# ESP32_xiaoneisai_20260831.net
KiCad netlist of a schematic drawn in EasyEDA Pro
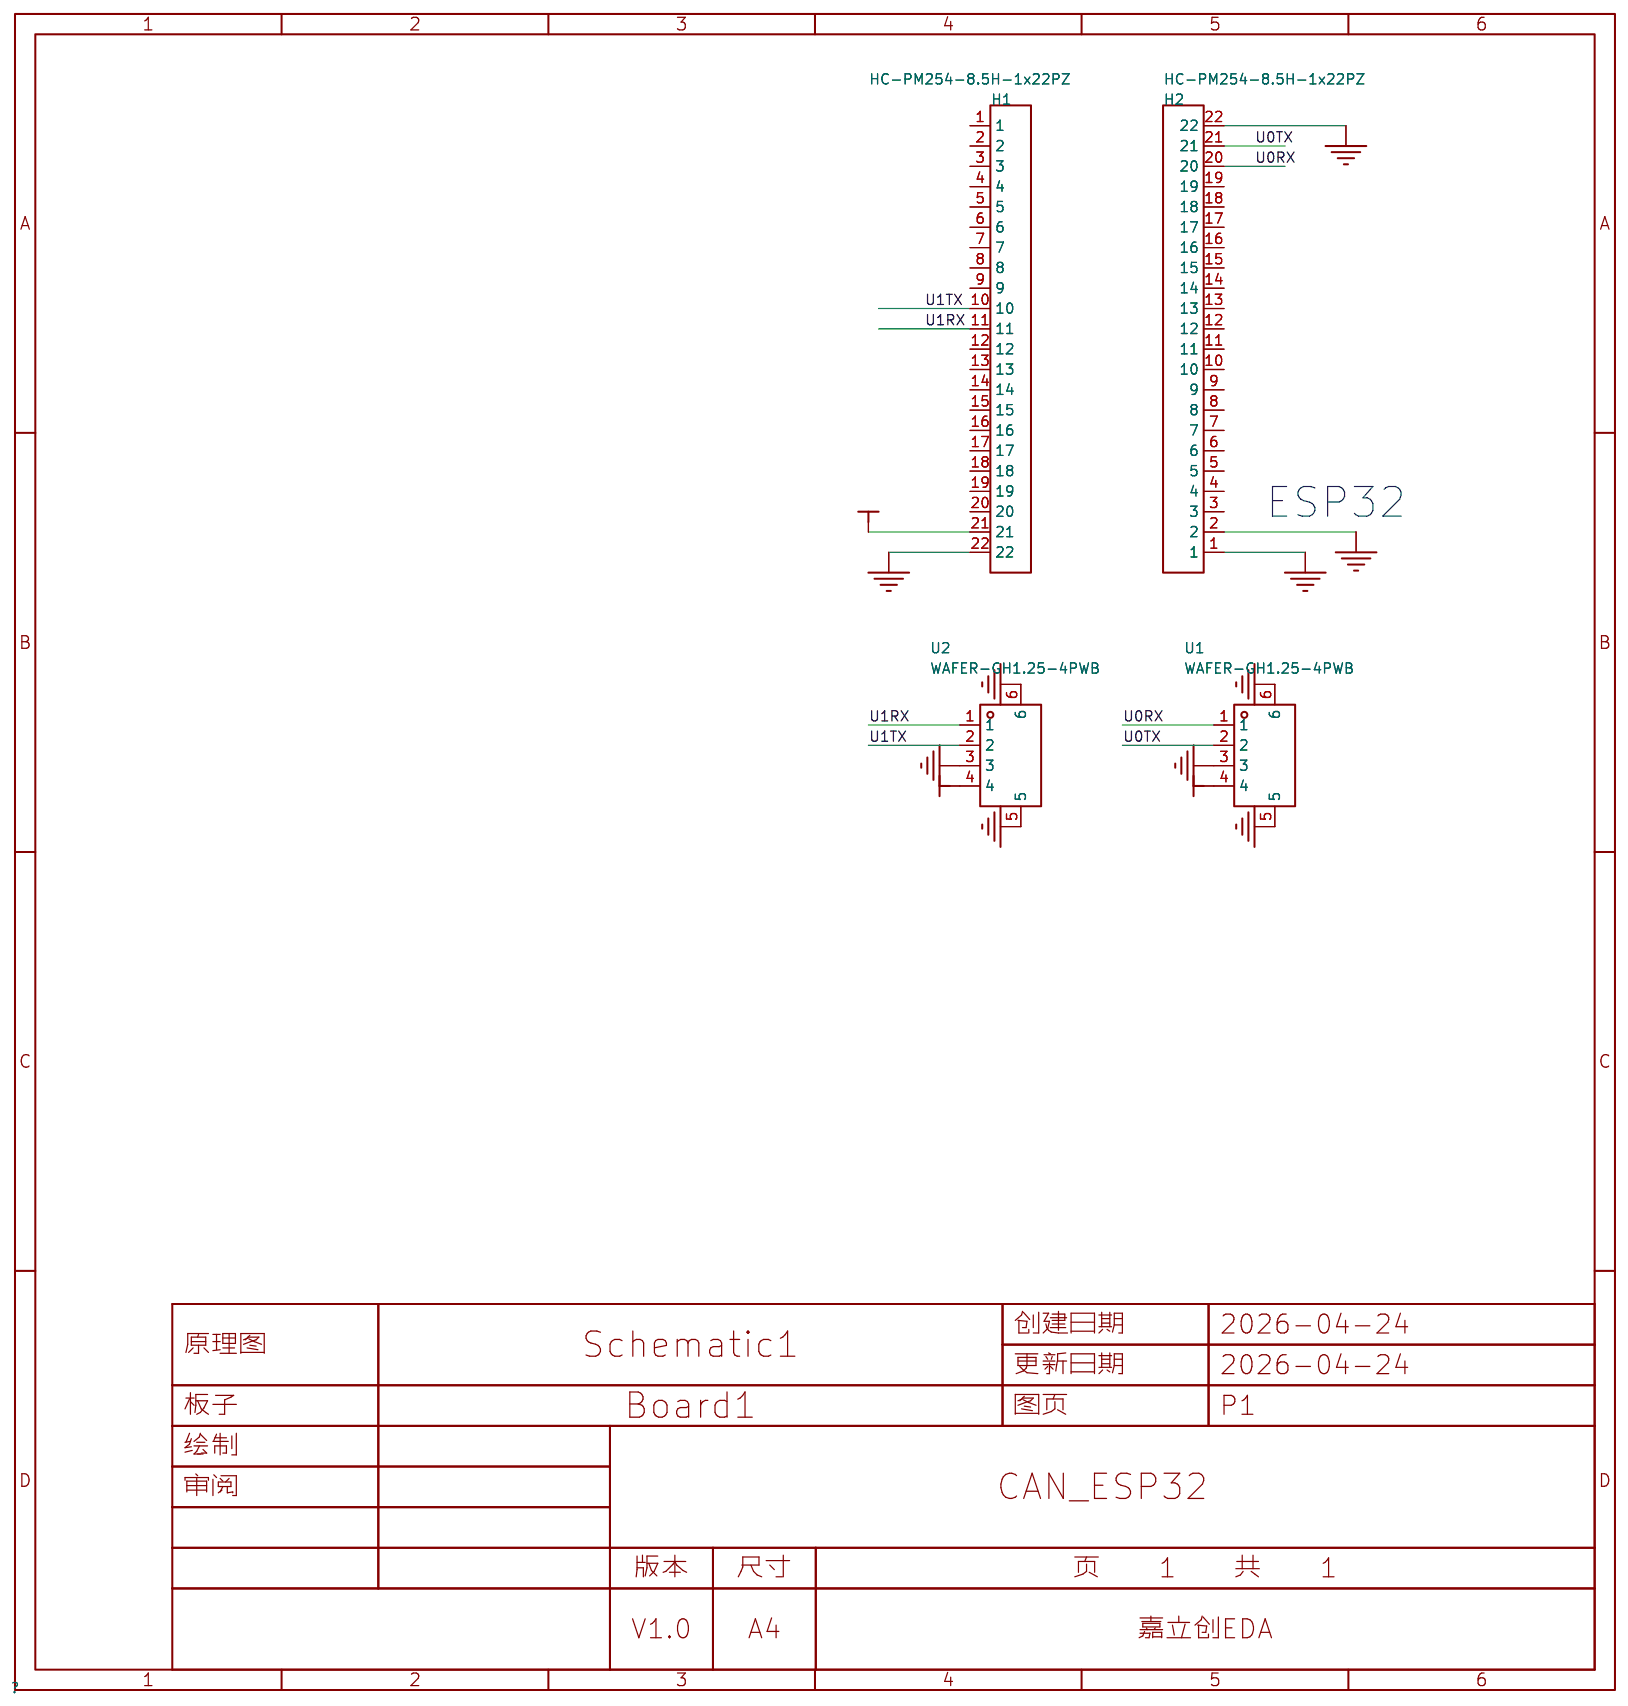
[diagram p0: schematic sheet]

(export (version "E")
  (design (tool "Eeschema 10.0.6"))
  (components
    (comp (ref "H1")
      (value "HC-PM254-8.5H-1x22PZ")
      (footprint "easyedapro:HDR-TH_22P-P2.54-V-F")
      (fields (field (name "Manufacturer") "HC(虹成电子)"))
      (libsource (lib "easyedapro") (part "HC-PM254-8.5H-1X22PZ"))
    )
    (comp (ref "H2")
      (value "HC-PM254-8.5H-1x22PZ")
      (footprint "easyedapro:HDR-TH_22P-P2.54-V-F")
      (fields (field (name "Manufacturer") "HC(虹成电子)"))
      (libsource (lib "easyedapro") (part "HC-PM254-8.5H-1X22PZ"))
    )
    (comp (ref "U1")
      (value "WAFER-GH1.25-4PWB")
      (footprint "easyedapro:CONN-SMD_4P-P1.25_XUNPU_WAFER-GH1.25-4PWB")
      (fields (field (name "Manufacturer") "XUNPU(讯普)"))
      (libsource (lib "easyedapro") (part "WAFER-GH1.25-4PWB"))
    )
    (comp (ref "U2")
      (value "WAFER-GH1.25-4PWB")
      (footprint "easyedapro:CONN-SMD_4P-P1.25_XUNPU_WAFER-GH1.25-4PWB")
      (fields (field (name "Manufacturer") "XUNPU(讯普)"))
      (libsource (lib "easyedapro") (part "WAFER-GH1.25-4PWB"))
    )
  )
  (nets
    (net (code "1") (name "/U0RX") (class "Default")
      (node (ref "H2") (pin "20") (pinfunction "20_20") (pintype "unspecified"))
      (node (ref "U1") (pin "1") (pinfunction "1_1") (pintype "unspecified"))
    )
    (net (code "2") (name "/U0TX") (class "Default")
      (node (ref "H2") (pin "21") (pinfunction "21_21") (pintype "unspecified"))
      (node (ref "U1") (pin "2") (pinfunction "2_2") (pintype "unspecified"))
    )
    (net (code "3") (name "/U1RX") (class "Default")
      (node (ref "H1") (pin "11") (pinfunction "11_11") (pintype "unspecified"))
      (node (ref "U2") (pin "1") (pinfunction "1_1") (pintype "unspecified"))
    )
    (net (code "4") (name "/U1TX") (class "Default")
      (node (ref "H1") (pin "10") (pinfunction "10_10") (pintype "unspecified"))
      (node (ref "U2") (pin "2") (pinfunction "2_2") (pintype "unspecified"))
    )
    (net (code "5") (name "GND") (class "Default")
      (node (ref "H1") (pin "22") (pinfunction "22_22") (pintype "unspecified"))
      (node (ref "H2") (pin "1") (pinfunction "1_1") (pintype "unspecified"))
      (node (ref "H2") (pin "2") (pinfunction "2_2") (pintype "unspecified"))
      (node (ref "H2") (pin "22") (pinfunction "22_22") (pintype "unspecified"))
      (node (ref "U1") (pin "3") (pinfunction "3_3") (pintype "unspecified"))
      (node (ref "U1") (pin "5") (pinfunction "5_5") (pintype "unspecified"))
      (node (ref "U1") (pin "6") (pinfunction "6_6") (pintype "unspecified"))
      (node (ref "U2") (pin "3") (pinfunction "3_3") (pintype "unspecified"))
      (node (ref "U2") (pin "5") (pinfunction "5_5") (pintype "unspecified"))
      (node (ref "U2") (pin "6") (pinfunction "6_6") (pintype "unspecified"))
    )
    (net (code "6") (name "VCC_5V") (class "Default")
      (node (ref "H1") (pin "21") (pinfunction "21_21") (pintype "unspecified"))
      (node (ref "U1") (pin "4") (pinfunction "4_4") (pintype "unspecified"))
      (node (ref "U2") (pin "4") (pinfunction "4_4") (pintype "unspecified"))
    )
    (net (code "7") (name "unconnected-(H1-Pad1)") (class "Default")
      (node (ref "H1") (pin "1") (pinfunction "1_1") (pintype "unspecified"))
    )
    (net (code "8") (name "unconnected-(H1-Pad2)") (class "Default")
      (node (ref "H1") (pin "2") (pinfunction "2_2") (pintype "unspecified"))
    )
    (net (code "9") (name "unconnected-(H1-Pad3)") (class "Default")
      (node (ref "H1") (pin "3") (pinfunction "3_3") (pintype "unspecified"))
    )
    (net (code "10") (name "unconnected-(H1-Pad4)") (class "Default")
      (node (ref "H1") (pin "4") (pinfunction "4_4") (pintype "unspecified"))
    )
    (net (code "11") (name "unconnected-(H1-Pad5)") (class "Default")
      (node (ref "H1") (pin "5") (pinfunction "5_5") (pintype "unspecified"))
    )
    (net (code "12") (name "unconnected-(H1-Pad6)") (class "Default")
      (node (ref "H1") (pin "6") (pinfunction "6_6") (pintype "unspecified"))
    )
    (net (code "13") (name "unconnected-(H1-Pad7)") (class "Default")
      (node (ref "H1") (pin "7") (pinfunction "7_7") (pintype "unspecified"))
    )
    (net (code "14") (name "unconnected-(H1-Pad8)") (class "Default")
      (node (ref "H1") (pin "8") (pinfunction "8_8") (pintype "unspecified"))
    )
    (net (code "15") (name "unconnected-(H1-Pad9)") (class "Default")
      (node (ref "H1") (pin "9") (pinfunction "9_9") (pintype "unspecified"))
    )
    (net (code "16") (name "unconnected-(H1-Pad12)") (class "Default")
      (node (ref "H1") (pin "12") (pinfunction "12_12") (pintype "unspecified"))
    )
    (net (code "17") (name "unconnected-(H1-Pad13)") (class "Default")
      (node (ref "H1") (pin "13") (pinfunction "13_13") (pintype "unspecified"))
    )
    (net (code "18") (name "unconnected-(H1-Pad14)") (class "Default")
      (node (ref "H1") (pin "14") (pinfunction "14_14") (pintype "unspecified"))
    )
    (net (code "19") (name "unconnected-(H1-Pad15)") (class "Default")
      (node (ref "H1") (pin "15") (pinfunction "15_15") (pintype "unspecified"))
    )
    (net (code "20") (name "unconnected-(H1-Pad16)") (class "Default")
      (node (ref "H1") (pin "16") (pinfunction "16_16") (pintype "unspecified"))
    )
    (net (code "21") (name "unconnected-(H1-Pad17)") (class "Default")
      (node (ref "H1") (pin "17") (pinfunction "17_17") (pintype "unspecified"))
    )
    (net (code "22") (name "unconnected-(H1-Pad18)") (class "Default")
      (node (ref "H1") (pin "18") (pinfunction "18_18") (pintype "unspecified"))
    )
    (net (code "23") (name "unconnected-(H1-Pad19)") (class "Default")
      (node (ref "H1") (pin "19") (pinfunction "19_19") (pintype "unspecified"))
    )
    (net (code "24") (name "unconnected-(H1-Pad20)") (class "Default")
      (node (ref "H1") (pin "20") (pinfunction "20_20") (pintype "unspecified"))
    )
    (net (code "25") (name "unconnected-(H2-Pad3)") (class "Default")
      (node (ref "H2") (pin "3") (pinfunction "3_3") (pintype "unspecified"))
    )
    (net (code "26") (name "unconnected-(H2-Pad4)") (class "Default")
      (node (ref "H2") (pin "4") (pinfunction "4_4") (pintype "unspecified"))
    )
    (net (code "27") (name "unconnected-(H2-Pad5)") (class "Default")
      (node (ref "H2") (pin "5") (pinfunction "5_5") (pintype "unspecified"))
    )
    (net (code "28") (name "unconnected-(H2-Pad6)") (class "Default")
      (node (ref "H2") (pin "6") (pinfunction "6_6") (pintype "unspecified"))
    )
    (net (code "29") (name "unconnected-(H2-Pad7)") (class "Default")
      (node (ref "H2") (pin "7") (pinfunction "7_7") (pintype "unspecified"))
    )
    (net (code "30") (name "unconnected-(H2-Pad8)") (class "Default")
      (node (ref "H2") (pin "8") (pinfunction "8_8") (pintype "unspecified"))
    )
    (net (code "31") (name "unconnected-(H2-Pad9)") (class "Default")
      (node (ref "H2") (pin "9") (pinfunction "9_9") (pintype "unspecified"))
    )
    (net (code "32") (name "unconnected-(H2-Pad10)") (class "Default")
      (node (ref "H2") (pin "10") (pinfunction "10_10") (pintype "unspecified"))
    )
    (net (code "33") (name "unconnected-(H2-Pad11)") (class "Default")
      (node (ref "H2") (pin "11") (pinfunction "11_11") (pintype "unspecified"))
    )
    (net (code "34") (name "unconnected-(H2-Pad12)") (class "Default")
      (node (ref "H2") (pin "12") (pinfunction "12_12") (pintype "unspecified"))
    )
    (net (code "35") (name "unconnected-(H2-Pad13)") (class "Default")
      (node (ref "H2") (pin "13") (pinfunction "13_13") (pintype "unspecified"))
    )
    (net (code "36") (name "unconnected-(H2-Pad14)") (class "Default")
      (node (ref "H2") (pin "14") (pinfunction "14_14") (pintype "unspecified"))
    )
    (net (code "37") (name "unconnected-(H2-Pad15)") (class "Default")
      (node (ref "H2") (pin "15") (pinfunction "15_15") (pintype "unspecified"))
    )
    (net (code "38") (name "unconnected-(H2-Pad16)") (class "Default")
      (node (ref "H2") (pin "16") (pinfunction "16_16") (pintype "unspecified"))
    )
    (net (code "39") (name "unconnected-(H2-Pad17)") (class "Default")
      (node (ref "H2") (pin "17") (pinfunction "17_17") (pintype "unspecified"))
    )
    (net (code "40") (name "unconnected-(H2-Pad18)") (class "Default")
      (node (ref "H2") (pin "18") (pinfunction "18_18") (pintype "unspecified"))
    )
    (net (code "41") (name "unconnected-(H2-Pad19)") (class "Default")
      (node (ref "H2") (pin "19") (pinfunction "19_19") (pintype "unspecified"))
    )
  )
)
